# led_pcb.net
KiCad netlist of a schematic drawn in EAGLE
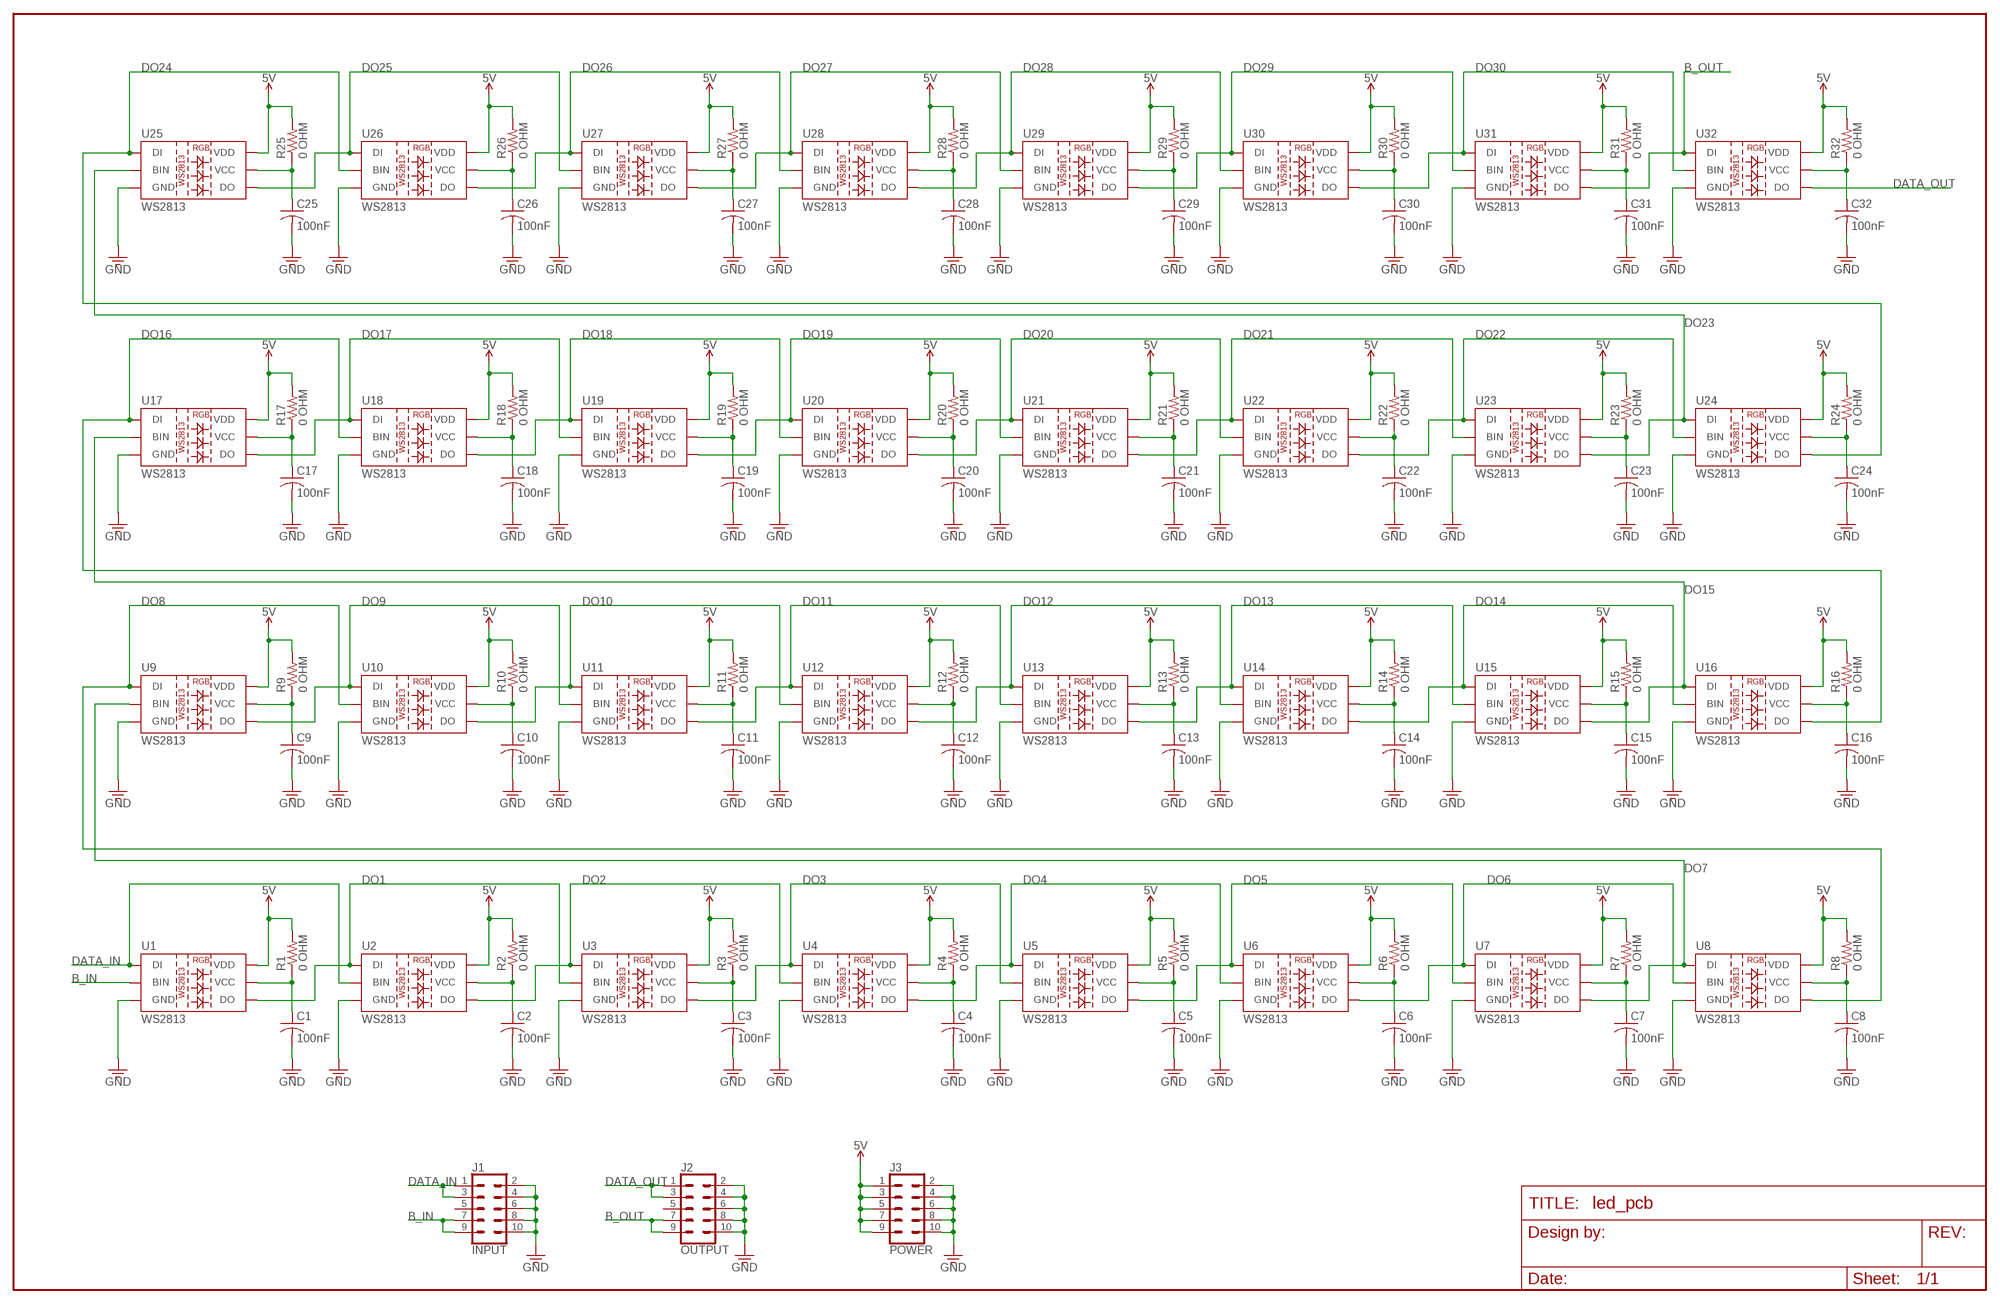
[diagram p0: schematic, sheet 1]

(export (version "E")
  (design (tool "Eeschema 10.0.6"))
  (components
    (comp (ref "C1")
      (value "100nF")
      (footprint "eagle-import:C0805K")
      (libsource (lib "eagle-import") (part "C-USC0805K"))
    )
    (comp (ref "C2")
      (value "100nF")
      (footprint "eagle-import:C0805K")
      (libsource (lib "eagle-import") (part "C-USC0805K"))
    )
    (comp (ref "C3")
      (value "100nF")
      (footprint "eagle-import:C0805K")
      (libsource (lib "eagle-import") (part "C-USC0805K"))
    )
    (comp (ref "C4")
      (value "100nF")
      (footprint "eagle-import:C0805K")
      (libsource (lib "eagle-import") (part "C-USC0805K"))
    )
    (comp (ref "C5")
      (value "100nF")
      (footprint "eagle-import:C0805K")
      (libsource (lib "eagle-import") (part "C-USC0805K"))
    )
    (comp (ref "C6")
      (value "100nF")
      (footprint "eagle-import:C0805K")
      (libsource (lib "eagle-import") (part "C-USC0805K"))
    )
    (comp (ref "C7")
      (value "100nF")
      (footprint "eagle-import:C0805K")
      (libsource (lib "eagle-import") (part "C-USC0805K"))
    )
    (comp (ref "C8")
      (value "100nF")
      (footprint "eagle-import:C0805K")
      (libsource (lib "eagle-import") (part "C-USC0805K"))
    )
    (comp (ref "C9")
      (value "100nF")
      (footprint "eagle-import:C0805K")
      (libsource (lib "eagle-import") (part "C-USC0805K"))
    )
    (comp (ref "C10")
      (value "100nF")
      (footprint "eagle-import:C0805K")
      (libsource (lib "eagle-import") (part "C-USC0805K"))
    )
    (comp (ref "C11")
      (value "100nF")
      (footprint "eagle-import:C0805K")
      (libsource (lib "eagle-import") (part "C-USC0805K"))
    )
    (comp (ref "C12")
      (value "100nF")
      (footprint "eagle-import:C0805K")
      (libsource (lib "eagle-import") (part "C-USC0805K"))
    )
    (comp (ref "C13")
      (value "100nF")
      (footprint "eagle-import:C0805K")
      (libsource (lib "eagle-import") (part "C-USC0805K"))
    )
    (comp (ref "C14")
      (value "100nF")
      (footprint "eagle-import:C0805K")
      (libsource (lib "eagle-import") (part "C-USC0805K"))
    )
    (comp (ref "C15")
      (value "100nF")
      (footprint "eagle-import:C0805K")
      (libsource (lib "eagle-import") (part "C-USC0805K"))
    )
    (comp (ref "C16")
      (value "100nF")
      (footprint "eagle-import:C0805K")
      (libsource (lib "eagle-import") (part "C-USC0805K"))
    )
    (comp (ref "C17")
      (value "100nF")
      (footprint "eagle-import:C0805K")
      (libsource (lib "eagle-import") (part "C-USC0805K"))
    )
    (comp (ref "C18")
      (value "100nF")
      (footprint "eagle-import:C0805K")
      (libsource (lib "eagle-import") (part "C-USC0805K"))
    )
    (comp (ref "C19")
      (value "100nF")
      (footprint "eagle-import:C0805K")
      (libsource (lib "eagle-import") (part "C-USC0805K"))
    )
    (comp (ref "C20")
      (value "100nF")
      (footprint "eagle-import:C0805K")
      (libsource (lib "eagle-import") (part "C-USC0805K"))
    )
    (comp (ref "C21")
      (value "100nF")
      (footprint "eagle-import:C0805K")
      (libsource (lib "eagle-import") (part "C-USC0805K"))
    )
    (comp (ref "C22")
      (value "100nF")
      (footprint "eagle-import:C0805K")
      (libsource (lib "eagle-import") (part "C-USC0805K"))
    )
    (comp (ref "C23")
      (value "100nF")
      (footprint "eagle-import:C0805K")
      (libsource (lib "eagle-import") (part "C-USC0805K"))
    )
    (comp (ref "C24")
      (value "100nF")
      (footprint "eagle-import:C0805K")
      (libsource (lib "eagle-import") (part "C-USC0805K"))
    )
    (comp (ref "C25")
      (value "100nF")
      (footprint "eagle-import:C0805K")
      (libsource (lib "eagle-import") (part "C-USC0805K"))
    )
    (comp (ref "C26")
      (value "100nF")
      (footprint "eagle-import:C0805K")
      (libsource (lib "eagle-import") (part "C-USC0805K"))
    )
    (comp (ref "C27")
      (value "100nF")
      (footprint "eagle-import:C0805K")
      (libsource (lib "eagle-import") (part "C-USC0805K"))
    )
    (comp (ref "C28")
      (value "100nF")
      (footprint "eagle-import:C0805K")
      (libsource (lib "eagle-import") (part "C-USC0805K"))
    )
    (comp (ref "C29")
      (value "100nF")
      (footprint "eagle-import:C0805K")
      (libsource (lib "eagle-import") (part "C-USC0805K"))
    )
    (comp (ref "C30")
      (value "100nF")
      (footprint "eagle-import:C0805K")
      (libsource (lib "eagle-import") (part "C-USC0805K"))
    )
    (comp (ref "C31")
      (value "100nF")
      (footprint "eagle-import:C0805K")
      (libsource (lib "eagle-import") (part "C-USC0805K"))
    )
    (comp (ref "C32")
      (value "100nF")
      (footprint "eagle-import:C0805K")
      (libsource (lib "eagle-import") (part "C-USC0805K"))
    )
    (comp (ref "J1")
      (value "INPUT")
      (footprint "eagle-import:2X5-SHROUDED_SMD")
      (libsource (lib "eagle-import") (part "CONN_05X2SHD_SMD"))
    )
    (comp (ref "J2")
      (value "OUTPUT")
      (footprint "eagle-import:2X5-SHROUDED_SMD")
      (libsource (lib "eagle-import") (part "CONN_05X2SHD_SMD"))
    )
    (comp (ref "J3")
      (value "POWER")
      (footprint "eagle-import:2X5-SHROUDED_SMD")
      (libsource (lib "eagle-import") (part "CONN_05X2SHD_SMD"))
    )
    (comp (ref "R1")
      (value "0 OHM")
      (footprint "eagle-import:M0805")
      (libsource (lib "eagle-import") (part "R-US_M0805"))
    )
    (comp (ref "R2")
      (value "0 OHM")
      (footprint "eagle-import:M0805")
      (libsource (lib "eagle-import") (part "R-US_M0805"))
    )
    (comp (ref "R3")
      (value "0 OHM")
      (footprint "eagle-import:M0805")
      (libsource (lib "eagle-import") (part "R-US_M0805"))
    )
    (comp (ref "R4")
      (value "0 OHM")
      (footprint "eagle-import:M0805")
      (libsource (lib "eagle-import") (part "R-US_M0805"))
    )
    (comp (ref "R5")
      (value "0 OHM")
      (footprint "eagle-import:M0805")
      (libsource (lib "eagle-import") (part "R-US_M0805"))
    )
    (comp (ref "R6")
      (value "0 OHM")
      (footprint "eagle-import:M0805")
      (libsource (lib "eagle-import") (part "R-US_M0805"))
    )
    (comp (ref "R7")
      (value "0 OHM")
      (footprint "eagle-import:M0805")
      (libsource (lib "eagle-import") (part "R-US_M0805"))
    )
    (comp (ref "R8")
      (value "0 OHM")
      (footprint "eagle-import:M0805")
      (libsource (lib "eagle-import") (part "R-US_M0805"))
    )
    (comp (ref "R9")
      (value "0 OHM")
      (footprint "eagle-import:M0805")
      (libsource (lib "eagle-import") (part "R-US_M0805"))
    )
    (comp (ref "R10")
      (value "0 OHM")
      (footprint "eagle-import:M0805")
      (libsource (lib "eagle-import") (part "R-US_M0805"))
    )
    (comp (ref "R11")
      (value "0 OHM")
      (footprint "eagle-import:M0805")
      (libsource (lib "eagle-import") (part "R-US_M0805"))
    )
    (comp (ref "R12")
      (value "0 OHM")
      (footprint "eagle-import:M0805")
      (libsource (lib "eagle-import") (part "R-US_M0805"))
    )
    (comp (ref "R13")
      (value "0 OHM")
      (footprint "eagle-import:M0805")
      (libsource (lib "eagle-import") (part "R-US_M0805"))
    )
    (comp (ref "R14")
      (value "0 OHM")
      (footprint "eagle-import:M0805")
      (libsource (lib "eagle-import") (part "R-US_M0805"))
    )
    (comp (ref "R15")
      (value "0 OHM")
      (footprint "eagle-import:M0805")
      (libsource (lib "eagle-import") (part "R-US_M0805"))
    )
    (comp (ref "R16")
      (value "0 OHM")
      (footprint "eagle-import:M0805")
      (libsource (lib "eagle-import") (part "R-US_M0805"))
    )
    (comp (ref "R17")
      (value "0 OHM")
      (footprint "eagle-import:M0805")
      (libsource (lib "eagle-import") (part "R-US_M0805"))
    )
    (comp (ref "R18")
      (value "0 OHM")
      (footprint "eagle-import:M0805")
      (libsource (lib "eagle-import") (part "R-US_M0805"))
    )
    (comp (ref "R19")
      (value "0 OHM")
      (footprint "eagle-import:M0805")
      (libsource (lib "eagle-import") (part "R-US_M0805"))
    )
    (comp (ref "R20")
      (value "0 OHM")
      (footprint "eagle-import:M0805")
      (libsource (lib "eagle-import") (part "R-US_M0805"))
    )
    (comp (ref "R21")
      (value "0 OHM")
      (footprint "eagle-import:M0805")
      (libsource (lib "eagle-import") (part "R-US_M0805"))
    )
    (comp (ref "R22")
      (value "0 OHM")
      (footprint "eagle-import:M0805")
      (libsource (lib "eagle-import") (part "R-US_M0805"))
    )
    (comp (ref "R23")
      (value "0 OHM")
      (footprint "eagle-import:M0805")
      (libsource (lib "eagle-import") (part "R-US_M0805"))
    )
    (comp (ref "R24")
      (value "0 OHM")
      (footprint "eagle-import:M0805")
      (libsource (lib "eagle-import") (part "R-US_M0805"))
    )
    (comp (ref "R25")
      (value "0 OHM")
      (footprint "eagle-import:M0805")
      (libsource (lib "eagle-import") (part "R-US_M0805"))
    )
    (comp (ref "R26")
      (value "0 OHM")
      (footprint "eagle-import:M0805")
      (libsource (lib "eagle-import") (part "R-US_M0805"))
    )
    (comp (ref "R27")
      (value "0 OHM")
      (footprint "eagle-import:M0805")
      (libsource (lib "eagle-import") (part "R-US_M0805"))
    )
    (comp (ref "R28")
      (value "0 OHM")
      (footprint "eagle-import:M0805")
      (libsource (lib "eagle-import") (part "R-US_M0805"))
    )
    (comp (ref "R29")
      (value "0 OHM")
      (footprint "eagle-import:M0805")
      (libsource (lib "eagle-import") (part "R-US_M0805"))
    )
    (comp (ref "R30")
      (value "0 OHM")
      (footprint "eagle-import:M0805")
      (libsource (lib "eagle-import") (part "R-US_M0805"))
    )
    (comp (ref "R31")
      (value "0 OHM")
      (footprint "eagle-import:M0805")
      (libsource (lib "eagle-import") (part "R-US_M0805"))
    )
    (comp (ref "R32")
      (value "0 OHM")
      (footprint "eagle-import:M0805")
      (libsource (lib "eagle-import") (part "R-US_M0805"))
    )
    (comp (ref "U1")
      (value "WS2813")
      (footprint "eagle-import:WS2813")
      (libsource (lib "eagle-import") (part "WS2813"))
    )
    (comp (ref "U2")
      (value "WS2813")
      (footprint "eagle-import:WS2813")
      (libsource (lib "eagle-import") (part "WS2813"))
    )
    (comp (ref "U3")
      (value "WS2813")
      (footprint "eagle-import:WS2813")
      (libsource (lib "eagle-import") (part "WS2813"))
    )
    (comp (ref "U4")
      (value "WS2813")
      (footprint "eagle-import:WS2813")
      (libsource (lib "eagle-import") (part "WS2813"))
    )
    (comp (ref "U5")
      (value "WS2813")
      (footprint "eagle-import:WS2813")
      (libsource (lib "eagle-import") (part "WS2813"))
    )
    (comp (ref "U6")
      (value "WS2813")
      (footprint "eagle-import:WS2813")
      (libsource (lib "eagle-import") (part "WS2813"))
    )
    (comp (ref "U7")
      (value "WS2813")
      (footprint "eagle-import:WS2813")
      (libsource (lib "eagle-import") (part "WS2813"))
    )
    (comp (ref "U8")
      (value "WS2813")
      (footprint "eagle-import:WS2813")
      (libsource (lib "eagle-import") (part "WS2813"))
    )
    (comp (ref "U9")
      (value "WS2813")
      (footprint "eagle-import:WS2813")
      (libsource (lib "eagle-import") (part "WS2813"))
    )
    (comp (ref "U10")
      (value "WS2813")
      (footprint "eagle-import:WS2813")
      (libsource (lib "eagle-import") (part "WS2813"))
    )
    (comp (ref "U11")
      (value "WS2813")
      (footprint "eagle-import:WS2813")
      (libsource (lib "eagle-import") (part "WS2813"))
    )
    (comp (ref "U12")
      (value "WS2813")
      (footprint "eagle-import:WS2813")
      (libsource (lib "eagle-import") (part "WS2813"))
    )
    (comp (ref "U13")
      (value "WS2813")
      (footprint "eagle-import:WS2813")
      (libsource (lib "eagle-import") (part "WS2813"))
    )
    (comp (ref "U14")
      (value "WS2813")
      (footprint "eagle-import:WS2813")
      (libsource (lib "eagle-import") (part "WS2813"))
    )
    (comp (ref "U15")
      (value "WS2813")
      (footprint "eagle-import:WS2813")
      (libsource (lib "eagle-import") (part "WS2813"))
    )
    (comp (ref "U16")
      (value "WS2813")
      (footprint "eagle-import:WS2813")
      (libsource (lib "eagle-import") (part "WS2813"))
    )
    (comp (ref "U17")
      (value "WS2813")
      (footprint "eagle-import:WS2813")
      (libsource (lib "eagle-import") (part "WS2813"))
    )
    (comp (ref "U18")
      (value "WS2813")
      (footprint "eagle-import:WS2813")
      (libsource (lib "eagle-import") (part "WS2813"))
    )
    (comp (ref "U19")
      (value "WS2813")
      (footprint "eagle-import:WS2813")
      (libsource (lib "eagle-import") (part "WS2813"))
    )
    (comp (ref "U20")
      (value "WS2813")
      (footprint "eagle-import:WS2813")
      (libsource (lib "eagle-import") (part "WS2813"))
    )
    (comp (ref "U21")
      (value "WS2813")
      (footprint "eagle-import:WS2813")
      (libsource (lib "eagle-import") (part "WS2813"))
    )
    (comp (ref "U22")
      (value "WS2813")
      (footprint "eagle-import:WS2813")
      (libsource (lib "eagle-import") (part "WS2813"))
    )
    (comp (ref "U23")
      (value "WS2813")
      (footprint "eagle-import:WS2813")
      (libsource (lib "eagle-import") (part "WS2813"))
    )
    (comp (ref "U24")
      (value "WS2813")
      (footprint "eagle-import:WS2813")
      (libsource (lib "eagle-import") (part "WS2813"))
    )
    (comp (ref "U25")
      (value "WS2813")
      (footprint "eagle-import:WS2813")
      (libsource (lib "eagle-import") (part "WS2813"))
    )
    (comp (ref "U26")
      (value "WS2813")
      (footprint "eagle-import:WS2813")
      (libsource (lib "eagle-import") (part "WS2813"))
    )
    (comp (ref "U27")
      (value "WS2813")
      (footprint "eagle-import:WS2813")
      (libsource (lib "eagle-import") (part "WS2813"))
    )
    (comp (ref "U28")
      (value "WS2813")
      (footprint "eagle-import:WS2813")
      (libsource (lib "eagle-import") (part "WS2813"))
    )
    (comp (ref "U29")
      (value "WS2813")
      (footprint "eagle-import:WS2813")
      (libsource (lib "eagle-import") (part "WS2813"))
    )
    (comp (ref "U30")
      (value "WS2813")
      (footprint "eagle-import:WS2813")
      (libsource (lib "eagle-import") (part "WS2813"))
    )
    (comp (ref "U31")
      (value "WS2813")
      (footprint "eagle-import:WS2813")
      (libsource (lib "eagle-import") (part "WS2813"))
    )
    (comp (ref "U32")
      (value "WS2813")
      (footprint "eagle-import:WS2813")
      (libsource (lib "eagle-import") (part "WS2813"))
    )
  )
  (nets
    (net (code "1") (name "/B_IN") (class "Default")
      (node (ref "J1") (pin "7") (pinfunction "7_7") (pintype "passive"))
      (node (ref "J1") (pin "9") (pinfunction "9_9") (pintype "passive"))
      (node (ref "U1") (pin "6") (pinfunction "BIN_6") (pintype "bidirectional"))
    )
    (net (code "2") (name "/B_OUT") (class "Default")
      (node (ref "J2") (pin "7") (pinfunction "7_7") (pintype "passive"))
      (node (ref "J2") (pin "9") (pinfunction "9_9") (pintype "passive"))
      (node (ref "U31") (pin "3") (pinfunction "DO_3") (pintype "bidirectional"))
      (node (ref "U32") (pin "4") (pinfunction "DI_4") (pintype "bidirectional"))
    )
    (net (code "3") (name "/DATA_IN") (class "Default")
      (node (ref "J1") (pin "1") (pinfunction "1_1") (pintype "passive"))
      (node (ref "J1") (pin "3") (pinfunction "3_3") (pintype "passive"))
      (node (ref "U1") (pin "4") (pinfunction "DI_4") (pintype "bidirectional"))
      (node (ref "U2") (pin "6") (pinfunction "BIN_6") (pintype "bidirectional"))
    )
    (net (code "4") (name "/DATA_OUT") (class "Default")
      (node (ref "J2") (pin "1") (pinfunction "1_1") (pintype "passive"))
      (node (ref "J2") (pin "3") (pinfunction "3_3") (pintype "passive"))
      (node (ref "U32") (pin "3") (pinfunction "DO_3") (pintype "bidirectional"))
    )
    (net (code "5") (name "/DO1") (class "Default")
      (node (ref "U1") (pin "3") (pinfunction "DO_3") (pintype "bidirectional"))
      (node (ref "U2") (pin "4") (pinfunction "DI_4") (pintype "bidirectional"))
      (node (ref "U3") (pin "6") (pinfunction "BIN_6") (pintype "bidirectional"))
    )
    (net (code "6") (name "/DO2") (class "Default")
      (node (ref "U2") (pin "3") (pinfunction "DO_3") (pintype "bidirectional"))
      (node (ref "U3") (pin "4") (pinfunction "DI_4") (pintype "bidirectional"))
      (node (ref "U4") (pin "6") (pinfunction "BIN_6") (pintype "bidirectional"))
    )
    (net (code "7") (name "/DO3") (class "Default")
      (node (ref "U3") (pin "3") (pinfunction "DO_3") (pintype "bidirectional"))
      (node (ref "U4") (pin "4") (pinfunction "DI_4") (pintype "bidirectional"))
      (node (ref "U5") (pin "6") (pinfunction "BIN_6") (pintype "bidirectional"))
    )
    (net (code "8") (name "/DO4") (class "Default")
      (node (ref "U4") (pin "3") (pinfunction "DO_3") (pintype "bidirectional"))
      (node (ref "U5") (pin "4") (pinfunction "DI_4") (pintype "bidirectional"))
      (node (ref "U6") (pin "6") (pinfunction "BIN_6") (pintype "bidirectional"))
    )
    (net (code "9") (name "/DO5") (class "Default")
      (node (ref "U5") (pin "3") (pinfunction "DO_3") (pintype "bidirectional"))
      (node (ref "U6") (pin "4") (pinfunction "DI_4") (pintype "bidirectional"))
      (node (ref "U7") (pin "6") (pinfunction "BIN_6") (pintype "bidirectional"))
    )
    (net (code "10") (name "/DO6") (class "Default")
      (node (ref "U6") (pin "3") (pinfunction "DO_3") (pintype "bidirectional"))
      (node (ref "U7") (pin "4") (pinfunction "DI_4") (pintype "bidirectional"))
      (node (ref "U8") (pin "6") (pinfunction "BIN_6") (pintype "bidirectional"))
    )
    (net (code "11") (name "/DO7") (class "Default")
      (node (ref "U7") (pin "3") (pinfunction "DO_3") (pintype "bidirectional"))
      (node (ref "U8") (pin "4") (pinfunction "DI_4") (pintype "bidirectional"))
      (node (ref "U9") (pin "6") (pinfunction "BIN_6") (pintype "bidirectional"))
    )
    (net (code "12") (name "/DO8") (class "Default")
      (node (ref "U10") (pin "6") (pinfunction "BIN_6") (pintype "bidirectional"))
      (node (ref "U8") (pin "3") (pinfunction "DO_3") (pintype "bidirectional"))
      (node (ref "U9") (pin "4") (pinfunction "DI_4") (pintype "bidirectional"))
    )
    (net (code "13") (name "/DO9") (class "Default")
      (node (ref "U10") (pin "4") (pinfunction "DI_4") (pintype "bidirectional"))
      (node (ref "U11") (pin "6") (pinfunction "BIN_6") (pintype "bidirectional"))
      (node (ref "U9") (pin "3") (pinfunction "DO_3") (pintype "bidirectional"))
    )
    (net (code "14") (name "/DO10") (class "Default")
      (node (ref "U10") (pin "3") (pinfunction "DO_3") (pintype "bidirectional"))
      (node (ref "U11") (pin "4") (pinfunction "DI_4") (pintype "bidirectional"))
      (node (ref "U12") (pin "6") (pinfunction "BIN_6") (pintype "bidirectional"))
    )
    (net (code "15") (name "/DO11") (class "Default")
      (node (ref "U11") (pin "3") (pinfunction "DO_3") (pintype "bidirectional"))
      (node (ref "U12") (pin "4") (pinfunction "DI_4") (pintype "bidirectional"))
      (node (ref "U13") (pin "6") (pinfunction "BIN_6") (pintype "bidirectional"))
    )
    (net (code "16") (name "/DO12") (class "Default")
      (node (ref "U12") (pin "3") (pinfunction "DO_3") (pintype "bidirectional"))
      (node (ref "U13") (pin "4") (pinfunction "DI_4") (pintype "bidirectional"))
      (node (ref "U14") (pin "6") (pinfunction "BIN_6") (pintype "bidirectional"))
    )
    (net (code "17") (name "/DO13") (class "Default")
      (node (ref "U13") (pin "3") (pinfunction "DO_3") (pintype "bidirectional"))
      (node (ref "U14") (pin "4") (pinfunction "DI_4") (pintype "bidirectional"))
      (node (ref "U15") (pin "6") (pinfunction "BIN_6") (pintype "bidirectional"))
    )
    (net (code "18") (name "/DO14") (class "Default")
      (node (ref "U14") (pin "3") (pinfunction "DO_3") (pintype "bidirectional"))
      (node (ref "U15") (pin "4") (pinfunction "DI_4") (pintype "bidirectional"))
      (node (ref "U16") (pin "6") (pinfunction "BIN_6") (pintype "bidirectional"))
    )
    (net (code "19") (name "/DO15") (class "Default")
      (node (ref "U15") (pin "3") (pinfunction "DO_3") (pintype "bidirectional"))
      (node (ref "U16") (pin "4") (pinfunction "DI_4") (pintype "bidirectional"))
      (node (ref "U17") (pin "6") (pinfunction "BIN_6") (pintype "bidirectional"))
    )
    (net (code "20") (name "/DO16") (class "Default")
      (node (ref "U16") (pin "3") (pinfunction "DO_3") (pintype "bidirectional"))
      (node (ref "U17") (pin "4") (pinfunction "DI_4") (pintype "bidirectional"))
      (node (ref "U18") (pin "6") (pinfunction "BIN_6") (pintype "bidirectional"))
    )
    (net (code "21") (name "/DO17") (class "Default")
      (node (ref "U17") (pin "3") (pinfunction "DO_3") (pintype "bidirectional"))
      (node (ref "U18") (pin "4") (pinfunction "DI_4") (pintype "bidirectional"))
      (node (ref "U19") (pin "6") (pinfunction "BIN_6") (pintype "bidirectional"))
    )
    (net (code "22") (name "/DO18") (class "Default")
      (node (ref "U18") (pin "3") (pinfunction "DO_3") (pintype "bidirectional"))
      (node (ref "U19") (pin "4") (pinfunction "DI_4") (pintype "bidirectional"))
      (node (ref "U20") (pin "6") (pinfunction "BIN_6") (pintype "bidirectional"))
    )
    (net (code "23") (name "/DO19") (class "Default")
      (node (ref "U19") (pin "3") (pinfunction "DO_3") (pintype "bidirectional"))
      (node (ref "U20") (pin "4") (pinfunction "DI_4") (pintype "bidirectional"))
      (node (ref "U21") (pin "6") (pinfunction "BIN_6") (pintype "bidirectional"))
    )
    (net (code "24") (name "/DO20") (class "Default")
      (node (ref "U20") (pin "3") (pinfunction "DO_3") (pintype "bidirectional"))
      (node (ref "U21") (pin "4") (pinfunction "DI_4") (pintype "bidirectional"))
      (node (ref "U22") (pin "6") (pinfunction "BIN_6") (pintype "bidirectional"))
    )
    (net (code "25") (name "/DO21") (class "Default")
      (node (ref "U21") (pin "3") (pinfunction "DO_3") (pintype "bidirectional"))
      (node (ref "U22") (pin "4") (pinfunction "DI_4") (pintype "bidirectional"))
      (node (ref "U23") (pin "6") (pinfunction "BIN_6") (pintype "bidirectional"))
    )
    (net (code "26") (name "/DO22") (class "Default")
      (node (ref "U22") (pin "3") (pinfunction "DO_3") (pintype "bidirectional"))
      (node (ref "U23") (pin "4") (pinfunction "DI_4") (pintype "bidirectional"))
      (node (ref "U24") (pin "6") (pinfunction "BIN_6") (pintype "bidirectional"))
    )
    (net (code "27") (name "/DO23") (class "Default")
      (node (ref "U23") (pin "3") (pinfunction "DO_3") (pintype "bidirectional"))
      (node (ref "U24") (pin "4") (pinfunction "DI_4") (pintype "bidirectional"))
      (node (ref "U25") (pin "6") (pinfunction "BIN_6") (pintype "bidirectional"))
    )
    (net (code "28") (name "/DO24") (class "Default")
      (node (ref "U24") (pin "3") (pinfunction "DO_3") (pintype "bidirectional"))
      (node (ref "U25") (pin "4") (pinfunction "DI_4") (pintype "bidirectional"))
      (node (ref "U26") (pin "6") (pinfunction "BIN_6") (pintype "bidirectional"))
    )
    (net (code "29") (name "/DO25") (class "Default")
      (node (ref "U25") (pin "3") (pinfunction "DO_3") (pintype "bidirectional"))
      (node (ref "U26") (pin "4") (pinfunction "DI_4") (pintype "bidirectional"))
      (node (ref "U27") (pin "6") (pinfunction "BIN_6") (pintype "bidirectional"))
    )
    (net (code "30") (name "/DO26") (class "Default")
      (node (ref "U26") (pin "3") (pinfunction "DO_3") (pintype "bidirectional"))
      (node (ref "U27") (pin "4") (pinfunction "DI_4") (pintype "bidirectional"))
      (node (ref "U28") (pin "6") (pinfunction "BIN_6") (pintype "bidirectional"))
    )
    (net (code "31") (name "/DO27") (class "Default")
      (node (ref "U27") (pin "3") (pinfunction "DO_3") (pintype "bidirectional"))
      (node (ref "U28") (pin "4") (pinfunction "DI_4") (pintype "bidirectional"))
      (node (ref "U29") (pin "6") (pinfunction "BIN_6") (pintype "bidirectional"))
    )
    (net (code "32") (name "/DO28") (class "Default")
      (node (ref "U28") (pin "3") (pinfunction "DO_3") (pintype "bidirectional"))
      (node (ref "U29") (pin "4") (pinfunction "DI_4") (pintype "bidirectional"))
      (node (ref "U30") (pin "6") (pinfunction "BIN_6") (pintype "bidirectional"))
    )
    (net (code "33") (name "/DO29") (class "Default")
      (node (ref "U29") (pin "3") (pinfunction "DO_3") (pintype "bidirectional"))
      (node (ref "U30") (pin "4") (pinfunction "DI_4") (pintype "bidirectional"))
      (node (ref "U31") (pin "6") (pinfunction "BIN_6") (pintype "bidirectional"))
    )
    (net (code "34") (name "/DO30") (class "Default")
      (node (ref "U30") (pin "3") (pinfunction "DO_3") (pintype "bidirectional"))
      (node (ref "U31") (pin "4") (pinfunction "DI_4") (pintype "bidirectional"))
      (node (ref "U32") (pin "6") (pinfunction "BIN_6") (pintype "bidirectional"))
    )
    (net (code "35") (name "5V") (class "Default")
      (node (ref "J3") (pin "1") (pinfunction "1_1") (pintype "passive"))
      (node (ref "J3") (pin "3") (pinfunction "3_3") (pintype "passive"))
      (node (ref "J3") (pin "5") (pinfunction "5_5") (pintype "passive"))
      (node (ref "J3") (pin "7") (pinfunction "7_7") (pintype "passive"))
      (node (ref "J3") (pin "9") (pinfunction "9_9") (pintype "passive"))
      (node (ref "R1") (pin "2") (pinfunction "2_2") (pintype "passive"))
      (node (ref "R10") (pin "2") (pinfunction "2_2") (pintype "passive"))
      (node (ref "R11") (pin "2") (pinfunction "2_2") (pintype "passive"))
      (node (ref "R12") (pin "2") (pinfunction "2_2") (pintype "passive"))
      (node (ref "R13") (pin "2") (pinfunction "2_2") (pintype "passive"))
      (node (ref "R14") (pin "2") (pinfunction "2_2") (pintype "passive"))
      (node (ref "R15") (pin "2") (pinfunction "2_2") (pintype "passive"))
      (node (ref "R16") (pin "2") (pinfunction "2_2") (pintype "passive"))
      (node (ref "R17") (pin "2") (pinfunction "2_2") (pintype "passive"))
      (node (ref "R18") (pin "2") (pinfunction "2_2") (pintype "passive"))
      (node (ref "R19") (pin "2") (pinfunction "2_2") (pintype "passive"))
      (node (ref "R2") (pin "2") (pinfunction "2_2") (pintype "passive"))
      (node (ref "R20") (pin "2") (pinfunction "2_2") (pintype "passive"))
      (node (ref "R21") (pin "2") (pinfunction "2_2") (pintype "passive"))
      (node (ref "R22") (pin "2") (pinfunction "2_2") (pintype "passive"))
      (node (ref "R23") (pin "2") (pinfunction "2_2") (pintype "passive"))
      (node (ref "R24") (pin "2") (pinfunction "2_2") (pintype "passive"))
      (node (ref "R25") (pin "2") (pinfunction "2_2") (pintype "passive"))
      (node (ref "R26") (pin "2") (pinfunction "2_2") (pintype "passive"))
      (node (ref "R27") (pin "2") (pinfunction "2_2") (pintype "passive"))
      (node (ref "R28") (pin "2") (pinfunction "2_2") (pintype "passive"))
      (node (ref "R29") (pin "2") (pinfunction "2_2") (pintype "passive"))
      (node (ref "R3") (pin "2") (pinfunction "2_2") (pintype "passive"))
      (node (ref "R30") (pin "2") (pinfunction "2_2") (pintype "passive"))
      (node (ref "R31") (pin "2") (pinfunction "2_2") (pintype "passive"))
      (node (ref "R32") (pin "2") (pinfunction "2_2") (pintype "passive"))
      (node (ref "R4") (pin "2") (pinfunction "2_2") (pintype "passive"))
      (node (ref "R5") (pin "2") (pinfunction "2_2") (pintype "passive"))
      (node (ref "R6") (pin "2") (pinfunction "2_2") (pintype "passive"))
      (node (ref "R7") (pin "2") (pinfunction "2_2") (pintype "passive"))
      (node (ref "R8") (pin "2") (pinfunction "2_2") (pintype "passive"))
      (node (ref "R9") (pin "2") (pinfunction "2_2") (pintype "passive"))
      (node (ref "U1") (pin "2") (pinfunction "VDD_2") (pintype "bidirectional"))
      (node (ref "U10") (pin "2") (pinfunction "VDD_2") (pintype "bidirectional"))
      (node (ref "U11") (pin "2") (pinfunction "VDD_2") (pintype "bidirectional"))
      (node (ref "U12") (pin "2") (pinfunction "VDD_2") (pintype "bidirectional"))
      (node (ref "U13") (pin "2") (pinfunction "VDD_2") (pintype "bidirectional"))
      (node (ref "U14") (pin "2") (pinfunction "VDD_2") (pintype "bidirectional"))
      (node (ref "U15") (pin "2") (pinfunction "VDD_2") (pintype "bidirectional"))
      (node (ref "U16") (pin "2") (pinfunction "VDD_2") (pintype "bidirectional"))
      (node (ref "U17") (pin "2") (pinfunction "VDD_2") (pintype "bidirectional"))
      (node (ref "U18") (pin "2") (pinfunction "VDD_2") (pintype "bidirectional"))
      (node (ref "U19") (pin "2") (pinfunction "VDD_2") (pintype "bidirectional"))
      (node (ref "U2") (pin "2") (pinfunction "VDD_2") (pintype "bidirectional"))
      (node (ref "U20") (pin "2") (pinfunction "VDD_2") (pintype "bidirectional"))
      (node (ref "U21") (pin "2") (pinfunction "VDD_2") (pintype "bidirectional"))
      (node (ref "U22") (pin "2") (pinfunction "VDD_2") (pintype "bidirectional"))
      (node (ref "U23") (pin "2") (pinfunction "VDD_2") (pintype "bidirectional"))
      (node (ref "U24") (pin "2") (pinfunction "VDD_2") (pintype "bidirectional"))
      (node (ref "U25") (pin "2") (pinfunction "VDD_2") (pintype "bidirectional"))
      (node (ref "U26") (pin "2") (pinfunction "VDD_2") (pintype "bidirectional"))
      (node (ref "U27") (pin "2") (pinfunction "VDD_2") (pintype "bidirectional"))
      (node (ref "U28") (pin "2") (pinfunction "VDD_2") (pintype "bidirectional"))
      (node (ref "U29") (pin "2") (pinfunction "VDD_2") (pintype "bidirectional"))
      (node (ref "U3") (pin "2") (pinfunction "VDD_2") (pintype "bidirectional"))
      (node (ref "U30") (pin "2") (pinfunction "VDD_2") (pintype "bidirectional"))
      (node (ref "U31") (pin "2") (pinfunction "VDD_2") (pintype "bidirectional"))
      (node (ref "U32") (pin "2") (pinfunction "VDD_2") (pintype "bidirectional"))
      (node (ref "U4") (pin "2") (pinfunction "VDD_2") (pintype "bidirectional"))
      (node (ref "U5") (pin "2") (pinfunction "VDD_2") (pintype "bidirectional"))
      (node (ref "U6") (pin "2") (pinfunction "VDD_2") (pintype "bidirectional"))
      (node (ref "U7") (pin "2") (pinfunction "VDD_2") (pintype "bidirectional"))
      (node (ref "U8") (pin "2") (pinfunction "VDD_2") (pintype "bidirectional"))
      (node (ref "U9") (pin "2") (pinfunction "VDD_2") (pintype "bidirectional"))
    )
    (net (code "36") (name "GND") (class "Default")
      (node (ref "C1") (pin "2") (pinfunction "2_2") (pintype "passive"))
      (node (ref "C10") (pin "2") (pinfunction "2_2") (pintype "passive"))
      (node (ref "C11") (pin "2") (pinfunction "2_2") (pintype "passive"))
      (node (ref "C12") (pin "2") (pinfunction "2_2") (pintype "passive"))
      (node (ref "C13") (pin "2") (pinfunction "2_2") (pintype "passive"))
      (node (ref "C14") (pin "2") (pinfunction "2_2") (pintype "passive"))
      (node (ref "C15") (pin "2") (pinfunction "2_2") (pintype "passive"))
      (node (ref "C16") (pin "2") (pinfunction "2_2") (pintype "passive"))
      (node (ref "C17") (pin "2") (pinfunction "2_2") (pintype "passive"))
      (node (ref "C18") (pin "2") (pinfunction "2_2") (pintype "passive"))
      (node (ref "C19") (pin "2") (pinfunction "2_2") (pintype "passive"))
      (node (ref "C2") (pin "2") (pinfunction "2_2") (pintype "passive"))
      (node (ref "C20") (pin "2") (pinfunction "2_2") (pintype "passive"))
      (node (ref "C21") (pin "2") (pinfunction "2_2") (pintype "passive"))
      (node (ref "C22") (pin "2") (pinfunction "2_2") (pintype "passive"))
      (node (ref "C23") (pin "2") (pinfunction "2_2") (pintype "passive"))
      (node (ref "C24") (pin "2") (pinfunction "2_2") (pintype "passive"))
      (node (ref "C25") (pin "2") (pinfunction "2_2") (pintype "passive"))
      (node (ref "C26") (pin "2") (pinfunction "2_2") (pintype "passive"))
      (node (ref "C27") (pin "2") (pinfunction "2_2") (pintype "passive"))
      (node (ref "C28") (pin "2") (pinfunction "2_2") (pintype "passive"))
      (node (ref "C29") (pin "2") (pinfunction "2_2") (pintype "passive"))
      (node (ref "C3") (pin "2") (pinfunction "2_2") (pintype "passive"))
      (node (ref "C30") (pin "2") (pinfunction "2_2") (pintype "passive"))
      (node (ref "C31") (pin "2") (pinfunction "2_2") (pintype "passive"))
      (node (ref "C32") (pin "2") (pinfunction "2_2") (pintype "passive"))
      (node (ref "C4") (pin "2") (pinfunction "2_2") (pintype "passive"))
      (node (ref "C5") (pin "2") (pinfunction "2_2") (pintype "passive"))
      (node (ref "C6") (pin "2") (pinfunction "2_2") (pintype "passive"))
      (node (ref "C7") (pin "2") (pinfunction "2_2") (pintype "passive"))
      (node (ref "C8") (pin "2") (pinfunction "2_2") (pintype "passive"))
      (node (ref "C9") (pin "2") (pinfunction "2_2") (pintype "passive"))
      (node (ref "J1") (pin "10") (pinfunction "10_10") (pintype "passive"))
      (node (ref "J1") (pin "2") (pinfunction "2_2") (pintype "passive"))
      (node (ref "J1") (pin "4") (pinfunction "4_4") (pintype "passive"))
      (node (ref "J1") (pin "6") (pinfunction "6_6") (pintype "passive"))
      (node (ref "J1") (pin "8") (pinfunction "8_8") (pintype "passive"))
      (node (ref "J2") (pin "10") (pinfunction "10_10") (pintype "passive"))
      (node (ref "J2") (pin "2") (pinfunction "2_2") (pintype "passive"))
      (node (ref "J2") (pin "4") (pinfunction "4_4") (pintype "passive"))
      (node (ref "J2") (pin "6") (pinfunction "6_6") (pintype "passive"))
      (node (ref "J2") (pin "8") (pinfunction "8_8") (pintype "passive"))
      (node (ref "J3") (pin "10") (pinfunction "10_10") (pintype "passive"))
      (node (ref "J3") (pin "2") (pinfunction "2_2") (pintype "passive"))
      (node (ref "J3") (pin "4") (pinfunction "4_4") (pintype "passive"))
      (node (ref "J3") (pin "6") (pinfunction "6_6") (pintype "passive"))
      (node (ref "J3") (pin "8") (pinfunction "8_8") (pintype "passive"))
      (node (ref "U1") (pin "5") (pinfunction "GND_5") (pintype "bidirectional"))
      (node (ref "U10") (pin "5") (pinfunction "GND_5") (pintype "bidirectional"))
      (node (ref "U11") (pin "5") (pinfunction "GND_5") (pintype "bidirectional"))
      (node (ref "U12") (pin "5") (pinfunction "GND_5") (pintype "bidirectional"))
      (node (ref "U13") (pin "5") (pinfunction "GND_5") (pintype "bidirectional"))
      (node (ref "U14") (pin "5") (pinfunction "GND_5") (pintype "bidirectional"))
      (node (ref "U15") (pin "5") (pinfunction "GND_5") (pintype "bidirectional"))
      (node (ref "U16") (pin "5") (pinfunction "GND_5") (pintype "bidirectional"))
      (node (ref "U17") (pin "5") (pinfunction "GND_5") (pintype "bidirectional"))
      (node (ref "U18") (pin "5") (pinfunction "GND_5") (pintype "bidirectional"))
      (node (ref "U19") (pin "5") (pinfunction "GND_5") (pintype "bidirectional"))
      (node (ref "U2") (pin "5") (pinfunction "GND_5") (pintype "bidirectional"))
      (node (ref "U20") (pin "5") (pinfunction "GND_5") (pintype "bidirectional"))
      (node (ref "U21") (pin "5") (pinfunction "GND_5") (pintype "bidirectional"))
      (node (ref "U22") (pin "5") (pinfunction "GND_5") (pintype "bidirectional"))
      (node (ref "U23") (pin "5") (pinfunction "GND_5") (pintype "bidirectional"))
      (node (ref "U24") (pin "5") (pinfunction "GND_5") (pintype "bidirectional"))
      (node (ref "U25") (pin "5") (pinfunction "GND_5") (pintype "bidirectional"))
      (node (ref "U26") (pin "5") (pinfunction "GND_5") (pintype "bidirectional"))
      (node (ref "U27") (pin "5") (pinfunction "GND_5") (pintype "bidirectional"))
      (node (ref "U28") (pin "5") (pinfunction "GND_5") (pintype "bidirectional"))
      (node (ref "U29") (pin "5") (pinfunction "GND_5") (pintype "bidirectional"))
      (node (ref "U3") (pin "5") (pinfunction "GND_5") (pintype "bidirectional"))
      (node (ref "U30") (pin "5") (pinfunction "GND_5") (pintype "bidirectional"))
      (node (ref "U31") (pin "5") (pinfunction "GND_5") (pintype "bidirectional"))
      (node (ref "U32") (pin "5") (pinfunction "GND_5") (pintype "bidirectional"))
      (node (ref "U4") (pin "5") (pinfunction "GND_5") (pintype "bidirectional"))
      (node (ref "U5") (pin "5") (pinfunction "GND_5") (pintype "bidirectional"))
      (node (ref "U6") (pin "5") (pinfunction "GND_5") (pintype "bidirectional"))
      (node (ref "U7") (pin "5") (pinfunction "GND_5") (pintype "bidirectional"))
      (node (ref "U8") (pin "5") (pinfunction "GND_5") (pintype "bidirectional"))
      (node (ref "U9") (pin "5") (pinfunction "GND_5") (pintype "bidirectional"))
    )
    (net (code "37") (name "Net-(U1-VCC)") (class "Default")
      (node (ref "C1") (pin "1") (pinfunction "1_1") (pintype "passive"))
      (node (ref "R1") (pin "1") (pinfunction "1_1") (pintype "passive"))
      (node (ref "U1") (pin "1") (pinfunction "VCC_1") (pintype "bidirectional"))
    )
    (net (code "38") (name "Net-(U2-VCC)") (class "Default")
      (node (ref "C2") (pin "1") (pinfunction "1_1") (pintype "passive"))
      (node (ref "R2") (pin "1") (pinfunction "1_1") (pintype "passive"))
      (node (ref "U2") (pin "1") (pinfunction "VCC_1") (pintype "bidirectional"))
    )
    (net (code "39") (name "Net-(U3-VCC)") (class "Default")
      (node (ref "C3") (pin "1") (pinfunction "1_1") (pintype "passive"))
      (node (ref "R3") (pin "1") (pinfunction "1_1") (pintype "passive"))
      (node (ref "U3") (pin "1") (pinfunction "VCC_1") (pintype "bidirectional"))
    )
    (net (code "40") (name "Net-(U4-VCC)") (class "Default")
      (node (ref "C4") (pin "1") (pinfunction "1_1") (pintype "passive"))
      (node (ref "R4") (pin "1") (pinfunction "1_1") (pintype "passive"))
      (node (ref "U4") (pin "1") (pinfunction "VCC_1") (pintype "bidirectional"))
    )
    (net (code "41") (name "Net-(U5-VCC)") (class "Default")
      (node (ref "C5") (pin "1") (pinfunction "1_1") (pintype "passive"))
      (node (ref "R5") (pin "1") (pinfunction "1_1") (pintype "passive"))
      (node (ref "U5") (pin "1") (pinfunction "VCC_1") (pintype "bidirectional"))
    )
    (net (code "42") (name "Net-(U6-VCC)") (class "Default")
      (node (ref "C6") (pin "1") (pinfunction "1_1") (pintype "passive"))
      (node (ref "R6") (pin "1") (pinfunction "1_1") (pintype "passive"))
      (node (ref "U6") (pin "1") (pinfunction "VCC_1") (pintype "bidirectional"))
    )
    (net (code "43") (name "Net-(U7-VCC)") (class "Default")
      (node (ref "C7") (pin "1") (pinfunction "1_1") (pintype "passive"))
      (node (ref "R7") (pin "1") (pinfunction "1_1") (pintype "passive"))
      (node (ref "U7") (pin "1") (pinfunction "VCC_1") (pintype "bidirectional"))
    )
    (net (code "44") (name "Net-(U8-VCC)") (class "Default")
      (node (ref "C8") (pin "1") (pinfunction "1_1") (pintype "passive"))
      (node (ref "R8") (pin "1") (pinfunction "1_1") (pintype "passive"))
      (node (ref "U8") (pin "1") (pinfunction "VCC_1") (pintype "bidirectional"))
    )
    (net (code "45") (name "Net-(U9-VCC)") (class "Default")
      (node (ref "C9") (pin "1") (pinfunction "1_1") (pintype "passive"))
      (node (ref "R9") (pin "1") (pinfunction "1_1") (pintype "passive"))
      (node (ref "U9") (pin "1") (pinfunction "VCC_1") (pintype "bidirectional"))
    )
    (net (code "46") (name "Net-(U10-VCC)") (class "Default")
      (node (ref "C10") (pin "1") (pinfunction "1_1") (pintype "passive"))
      (node (ref "R10") (pin "1") (pinfunction "1_1") (pintype "passive"))
      (node (ref "U10") (pin "1") (pinfunction "VCC_1") (pintype "bidirectional"))
    )
    (net (code "47") (name "Net-(U11-VCC)") (class "Default")
      (node (ref "C11") (pin "1") (pinfunction "1_1") (pintype "passive"))
      (node (ref "R11") (pin "1") (pinfunction "1_1") (pintype "passive"))
      (node (ref "U11") (pin "1") (pinfunction "VCC_1") (pintype "bidirectional"))
    )
    (net (code "48") (name "Net-(U12-VCC)") (class "Default")
      (node (ref "C12") (pin "1") (pinfunction "1_1") (pintype "passive"))
      (node (ref "R12") (pin "1") (pinfunction "1_1") (pintype "passive"))
      (node (ref "U12") (pin "1") (pinfunction "VCC_1") (pintype "bidirectional"))
    )
    (net (code "49") (name "Net-(U13-VCC)") (class "Default")
      (node (ref "C13") (pin "1") (pinfunction "1_1") (pintype "passive"))
      (node (ref "R13") (pin "1") (pinfunction "1_1") (pintype "passive"))
      (node (ref "U13") (pin "1") (pinfunction "VCC_1") (pintype "bidirectional"))
    )
    (net (code "50") (name "Net-(U14-VCC)") (class "Default")
      (node (ref "C14") (pin "1") (pinfunction "1_1") (pintype "passive"))
      (node (ref "R14") (pin "1") (pinfunction "1_1") (pintype "passive"))
      (node (ref "U14") (pin "1") (pinfunction "VCC_1") (pintype "bidirectional"))
    )
    (net (code "51") (name "Net-(U15-VCC)") (class "Default")
      (node (ref "C15") (pin "1") (pinfunction "1_1") (pintype "passive"))
      (node (ref "R15") (pin "1") (pinfunction "1_1") (pintype "passive"))
      (node (ref "U15") (pin "1") (pinfunction "VCC_1") (pintype "bidirectional"))
    )
    (net (code "52") (name "Net-(U16-VCC)") (class "Default")
      (node (ref "C16") (pin "1") (pinfunction "1_1") (pintype "passive"))
      (node (ref "R16") (pin "1") (pinfunction "1_1") (pintype "passive"))
      (node (ref "U16") (pin "1") (pinfunction "VCC_1") (pintype "bidirectional"))
    )
    (net (code "53") (name "Net-(U17-VCC)") (class "Default")
      (node (ref "C17") (pin "1") (pinfunction "1_1") (pintype "passive"))
      (node (ref "R17") (pin "1") (pinfunction "1_1") (pintype "passive"))
      (node (ref "U17") (pin "1") (pinfunction "VCC_1") (pintype "bidirectional"))
    )
    (net (code "54") (name "Net-(U18-VCC)") (class "Default")
      (node (ref "C18") (pin "1") (pinfunction "1_1") (pintype "passive"))
      (node (ref "R18") (pin "1") (pinfunction "1_1") (pintype "passive"))
      (node (ref "U18") (pin "1") (pinfunction "VCC_1") (pintype "bidirectional"))
    )
    (net (code "55") (name "Net-(U19-VCC)") (class "Default")
      (node (ref "C19") (pin "1") (pinfunction "1_1") (pintype "passive"))
      (node (ref "R19") (pin "1") (pinfunction "1_1") (pintype "passive"))
      (node (ref "U19") (pin "1") (pinfunction "VCC_1") (pintype "bidirectional"))
    )
    (net (code "56") (name "Net-(U20-VCC)") (class "Default")
      (node (ref "C20") (pin "1") (pinfunction "1_1") (pintype "passive"))
      (node (ref "R20") (pin "1") (pinfunction "1_1") (pintype "passive"))
      (node (ref "U20") (pin "1") (pinfunction "VCC_1") (pintype "bidirectional"))
    )
    (net (code "57") (name "Net-(U21-VCC)") (class "Default")
      (node (ref "C21") (pin "1") (pinfunction "1_1") (pintype "passive"))
      (node (ref "R21") (pin "1") (pinfunction "1_1") (pintype "passive"))
      (node (ref "U21") (pin "1") (pinfunction "VCC_1") (pintype "bidirectional"))
    )
    (net (code "58") (name "Net-(U22-VCC)") (class "Default")
      (node (ref "C22") (pin "1") (pinfunction "1_1") (pintype "passive"))
      (node (ref "R22") (pin "1") (pinfunction "1_1") (pintype "passive"))
      (node (ref "U22") (pin "1") (pinfunction "VCC_1") (pintype "bidirectional"))
    )
    (net (code "59") (name "Net-(U23-VCC)") (class "Default")
      (node (ref "C23") (pin "1") (pinfunction "1_1") (pintype "passive"))
      (node (ref "R23") (pin "1") (pinfunction "1_1") (pintype "passive"))
      (node (ref "U23") (pin "1") (pinfunction "VCC_1") (pintype "bidirectional"))
    )
    (net (code "60") (name "Net-(U24-VCC)") (class "Default")
      (node (ref "C24") (pin "1") (pinfunction "1_1") (pintype "passive"))
      (node (ref "R24") (pin "1") (pinfunction "1_1") (pintype "passive"))
      (node (ref "U24") (pin "1") (pinfunction "VCC_1") (pintype "bidirectional"))
    )
    (net (code "61") (name "Net-(U25-VCC)") (class "Default")
      (node (ref "C25") (pin "1") (pinfunction "1_1") (pintype "passive"))
      (node (ref "R25") (pin "1") (pinfunction "1_1") (pintype "passive"))
      (node (ref "U25") (pin "1") (pinfunction "VCC_1") (pintype "bidirectional"))
    )
    (net (code "62") (name "Net-(U26-VCC)") (class "Default")
      (node (ref "C26") (pin "1") (pinfunction "1_1") (pintype "passive"))
      (node (ref "R26") (pin "1") (pinfunction "1_1") (pintype "passive"))
      (node (ref "U26") (pin "1") (pinfunction "VCC_1") (pintype "bidirectional"))
    )
    (net (code "63") (name "Net-(U27-VCC)") (class "Default")
      (node (ref "C27") (pin "1") (pinfunction "1_1") (pintype "passive"))
      (node (ref "R27") (pin "1") (pinfunction "1_1") (pintype "passive"))
      (node (ref "U27") (pin "1") (pinfunction "VCC_1") (pintype "bidirectional"))
    )
    (net (code "64") (name "Net-(U28-VCC)") (class "Default")
      (node (ref "C28") (pin "1") (pinfunction "1_1") (pintype "passive"))
      (node (ref "R28") (pin "1") (pinfunction "1_1") (pintype "passive"))
      (node (ref "U28") (pin "1") (pinfunction "VCC_1") (pintype "bidirectional"))
    )
    (net (code "65") (name "Net-(U29-VCC)") (class "Default")
      (node (ref "C29") (pin "1") (pinfunction "1_1") (pintype "passive"))
      (node (ref "R29") (pin "1") (pinfunction "1_1") (pintype "passive"))
      (node (ref "U29") (pin "1") (pinfunction "VCC_1") (pintype "bidirectional"))
    )
    (net (code "66") (name "Net-(U30-VCC)") (class "Default")
      (node (ref "C30") (pin "1") (pinfunction "1_1") (pintype "passive"))
      (node (ref "R30") (pin "1") (pinfunction "1_1") (pintype "passive"))
      (node (ref "U30") (pin "1") (pinfunction "VCC_1") (pintype "bidirectional"))
    )
    (net (code "67") (name "Net-(U31-VCC)") (class "Default")
      (node (ref "C31") (pin "1") (pinfunction "1_1") (pintype "passive"))
      (node (ref "R31") (pin "1") (pinfunction "1_1") (pintype "passive"))
      (node (ref "U31") (pin "1") (pinfunction "VCC_1") (pintype "bidirectional"))
    )
    (net (code "68") (name "Net-(U32-VCC)") (class "Default")
      (node (ref "C32") (pin "1") (pinfunction "1_1") (pintype "passive"))
      (node (ref "R32") (pin "1") (pinfunction "1_1") (pintype "passive"))
      (node (ref "U32") (pin "1") (pinfunction "VCC_1") (pintype "bidirectional"))
    )
    (net (code "69") (name "unconnected-(J1-Pad5)") (class "Default")
      (node (ref "J1") (pin "5") (pinfunction "5_5") (pintype "passive"))
    )
    (net (code "70") (name "unconnected-(J2-Pad5)") (class "Default")
      (node (ref "J2") (pin "5") (pinfunction "5_5") (pintype "passive"))
    )
  )
)
